# schBeagleBone.net
KiCad netlist of a schematic drawn in Altium Designer
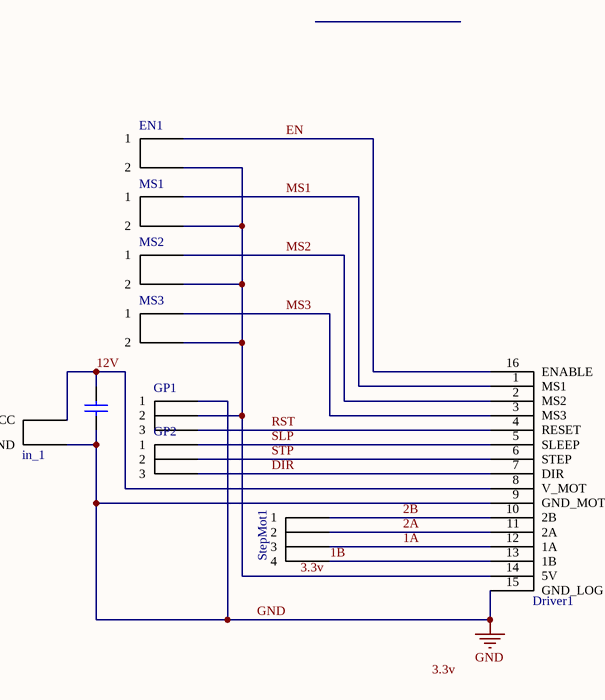
[diagram p0: schBeagleBone.SchDoc]

(export (version "E")
  (design (tool "Eeschema 10.0.6"))
  (components
    (comp (ref "C1")
      (value "Cap")
      (footprint "RAD-0.3")
      (description "Capacitor")
      (fields (field (name "PUBLISHER") "Altium Limited"))
      (libsource (lib "Miscellaneous Devices") (part "Cap"))
    )
    (comp (ref "Driver1")
      (value "A4988")
      (footprint "A4988")
      (libsource (lib "Componentes_Open") (part "A4988"))
    )
    (comp (ref "EN1")
      (value "KK2")
      (footprint "2-vias")
      (libsource (lib "Componentes_Open") (part "KK2Vias"))
    )
    (comp (ref "GP1")
      (value "KK3")
      (footprint "3-vias")
      (libsource (lib "Componentes_Open") (part "KK3Vias"))
    )
    (comp (ref "GP2")
      (value "KK3")
      (footprint "3-vias")
      (libsource (lib "Componentes_Open") (part "KK3Vias"))
    )
    (comp (ref "in_1")
      (value "Jack")
      (footprint "JACK J4")
      (libsource (lib "Componentes_Open") (part "Jack"))
    )
    (comp (ref "MS1")
      (value "KK2")
      (footprint "2-vias")
      (libsource (lib "Componentes_Open") (part "KK2Vias"))
    )
    (comp (ref "MS2")
      (value "KK2")
      (footprint "2-vias")
      (libsource (lib "Componentes_Open") (part "KK2Vias"))
    )
    (comp (ref "MS3")
      (value "KK2")
      (footprint "2-vias")
      (libsource (lib "Componentes_Open") (part "KK2Vias"))
    )
    (comp (ref "StepMot1")
      (value "KK4")
      (footprint "4-vias")
      (libsource (lib "Componentes_Open") (part "KK4Vias"))
    )
  )
  (nets
    (net (code "1") (name "/1A") (class "Default")
      (node (ref "Driver1") (pin "12") (pinfunction "1A_12") (pintype "passive"))
      (node (ref "StepMot1") (pin "3") (pinfunction "3_3") (pintype "passive"))
    )
    (net (code "2") (name "/1B") (class "Default")
      (node (ref "Driver1") (pin "13") (pinfunction "1B_13") (pintype "passive"))
      (node (ref "StepMot1") (pin "4") (pinfunction "4_4") (pintype "passive"))
    )
    (net (code "3") (name "/2A") (class "Default")
      (node (ref "Driver1") (pin "11") (pinfunction "2A_11") (pintype "passive"))
      (node (ref "StepMot1") (pin "2") (pinfunction "2_2") (pintype "passive"))
    )
    (net (code "4") (name "/2B") (class "Default")
      (node (ref "Driver1") (pin "10") (pinfunction "2B_10") (pintype "passive"))
      (node (ref "StepMot1") (pin "1") (pinfunction "1_1") (pintype "passive"))
    )
    (net (code "5") (name "/3.3v") (class "Default")
      (node (ref "Driver1") (pin "14") (pinfunction "5V_14") (pintype "passive"))
      (node (ref "EN1") (pin "2") (pinfunction "2_2") (pintype "passive"))
      (node (ref "GP1") (pin "2") (pinfunction "2_2") (pintype "passive"))
      (node (ref "MS1") (pin "2") (pinfunction "2_2") (pintype "passive"))
      (node (ref "MS2") (pin "2") (pinfunction "2_2") (pintype "passive"))
      (node (ref "MS3") (pin "2") (pinfunction "2_2") (pintype "passive"))
    )
    (net (code "6") (name "/12V") (class "Default")
      (node (ref "C1") (pin "2") (pinfunction "2_2") (pintype "passive"))
      (node (ref "Driver1") (pin "8") (pinfunction "V_MOT_8") (pintype "passive"))
      (node (ref "in_1") (pin "1") (pinfunction "VCC_1") (pintype "passive"))
    )
    (net (code "7") (name "/DIR") (class "Default")
      (node (ref "Driver1") (pin "7") (pinfunction "DIR_7") (pintype "passive"))
      (node (ref "GP2") (pin "3") (pinfunction "3_3") (pintype "passive"))
    )
    (net (code "8") (name "/EN") (class "Default")
      (node (ref "Driver1") (pin "16") (pinfunction "ENABLE_16") (pintype "passive"))
      (node (ref "EN1") (pin "1") (pinfunction "1_1") (pintype "passive"))
    )
    (net (code "9") (name "/MS1") (class "Default")
      (node (ref "Driver1") (pin "1") (pinfunction "MS1_1") (pintype "passive"))
      (node (ref "MS1") (pin "1") (pinfunction "1_1") (pintype "passive"))
    )
    (net (code "10") (name "/MS2") (class "Default")
      (node (ref "Driver1") (pin "2") (pinfunction "MS2_2") (pintype "passive"))
      (node (ref "MS2") (pin "1") (pinfunction "1_1") (pintype "passive"))
    )
    (net (code "11") (name "/MS3") (class "Default")
      (node (ref "Driver1") (pin "3") (pinfunction "MS3_3") (pintype "passive"))
      (node (ref "MS3") (pin "1") (pinfunction "1_1") (pintype "passive"))
    )
    (net (code "12") (name "/RST") (class "Default")
      (node (ref "Driver1") (pin "4") (pinfunction "RESET_4") (pintype "passive"))
      (node (ref "GP1") (pin "3") (pinfunction "3_3") (pintype "passive"))
    )
    (net (code "13") (name "/SLP") (class "Default")
      (node (ref "Driver1") (pin "5") (pinfunction "SLEEP_5") (pintype "passive"))
      (node (ref "GP2") (pin "1") (pinfunction "1_1") (pintype "passive"))
    )
    (net (code "14") (name "/STP") (class "Default")
      (node (ref "Driver1") (pin "6") (pinfunction "STEP_6") (pintype "passive"))
      (node (ref "GP2") (pin "2") (pinfunction "2_2") (pintype "passive"))
    )
    (net (code "15") (name "GND") (class "Default")
      (node (ref "C1") (pin "1") (pinfunction "1_1") (pintype "passive"))
      (node (ref "Driver1") (pin "15") (pinfunction "GND_LOG_15") (pintype "passive"))
      (node (ref "Driver1") (pin "9") (pinfunction "GND_MOT_9") (pintype "passive"))
      (node (ref "GP1") (pin "1") (pinfunction "1_1") (pintype "passive"))
      (node (ref "in_1") (pin "2") (pinfunction "GND_2") (pintype "passive"))
    )
  )
)
